# Alimentacion.net
KiCad netlist of a schematic drawn in Altium Designer
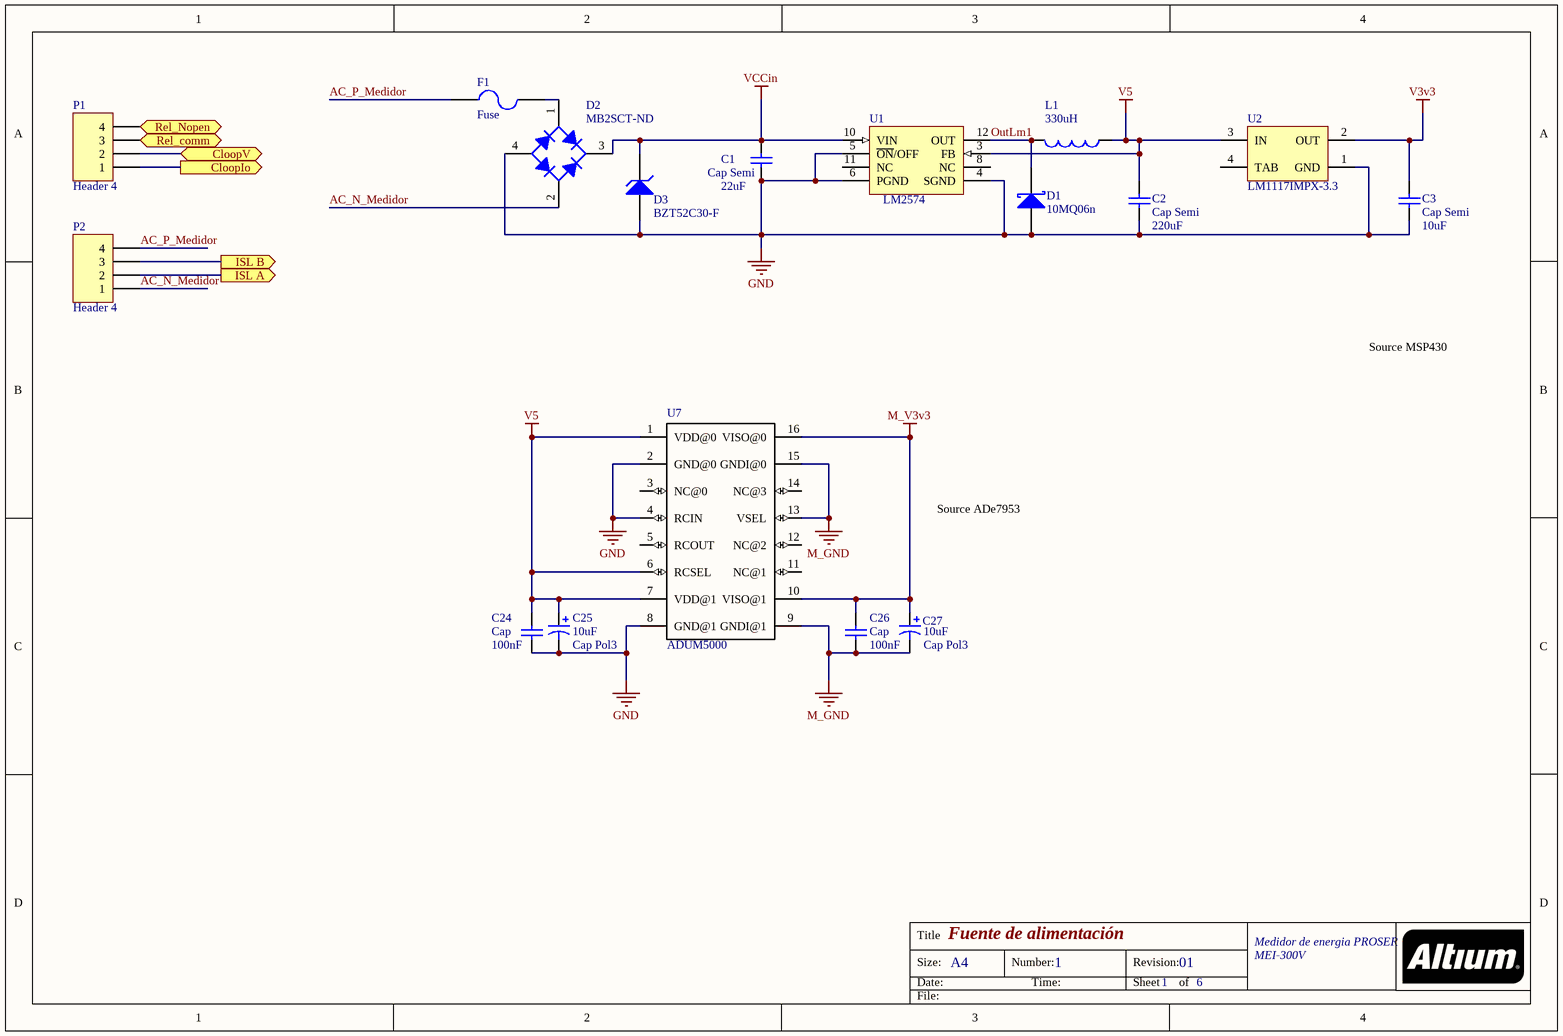
[diagram p0: Alimentacion.SchDoc]

(export (version "E")
  (design (tool "Eeschema 10.0.6"))
  (components
    (comp (ref "C1")
      (value "Cap Semi")
      (footprint "7343")
      (description "Capacitor (Semiconductor SIM Model)")
      (fields (field (name "ALTIUM_VALUE") "22uF") (field (name "PUBLISHER") "Altium Limited"))
      (libsource (lib "Miscellaneous Devices") (part "Cap Semi"))
    )
    (comp (ref "C2")
      (value "Cap Semi")
      (footprint "7343")
      (description "Capacitor (Semiconductor SIM Model)")
      (fields (field (name "ALTIUM_VALUE") "220uF") (field (name "PUBLISHER") "Altium Limited"))
      (libsource (lib "Miscellaneous Devices") (part "Sym"))
    )
    (comp (ref "C3")
      (value "Cap Semi")
      (footprint "3528")
      (description "Capacitor (Semiconductor SIM Model)")
      (fields (field (name "ALTIUM_VALUE") "10uF") (field (name "PUBLISHER") "Altium Limited"))
      (libsource (lib "Miscellaneous Devices") (part "Cap Semi"))
    )
    (comp (ref "C24")
      (value "Cap")
      (footprint "Custom0805")
      (description "Capacitor")
      (fields (field (name "ALTIUM_VALUE") "100nF") (field (name "PUBLISHER") "Altium Limited"))
      (libsource (lib "Miscellaneous Devices") (part "Cap"))
    )
    (comp (ref "C25")
      (value "Cap Pol3")
      (footprint "3528")
      (description "Polarized Capacitor (Surface Mount)")
      (fields (field (name "ALTIUM_VALUE") "10uF") (field (name "PUBLISHER") "Altium Limited"))
      (libsource (lib "Miscellaneous Devices") (part "Cap Pol3"))
    )
    (comp (ref "C26")
      (value "Cap")
      (footprint "Custom0805")
      (description "Capacitor")
      (fields (field (name "ALTIUM_VALUE") "100nF") (field (name "PUBLISHER") "Altium Limited"))
      (libsource (lib "Miscellaneous Devices") (part "Cap"))
    )
    (comp (ref "C27")
      (value "Cap Pol3")
      (footprint "3528")
      (description "Polarized Capacitor (Surface Mount)")
      (fields (field (name "ALTIUM_VALUE") "10uF") (field (name "PUBLISHER") "Altium Limited"))
      (libsource (lib "Miscellaneous Devices") (part "Cap Pol3"))
    )
    (comp (ref "D1")
      (value "10MQ06n")
      (footprint "DO214")
      (description "Schottky Diode")
      (fields (field (name "PUBLISHER") "Altium Limited"))
      (libsource (lib "Miscellaneous Devices") (part "D Schottky"))
    )
    (comp (ref "D2")
      (value "MB2SCT-ND")
      (footprint "SOIC4_M")
      (description "Full Wave Diode Bridge - MB2S")
      (fields (field (name "PUBLISHER") "Altium Limited"))
      (libsource (lib "Miscellaneous Devices") (part "Bridge1"))
    )
    (comp (ref "D3")
      (value "BZT52C30-F")
      (footprint "1N4148W")
      (description "Zener Diode SMD")
      (fields (field (name "PUBLISHER") "Altium Limited"))
      (libsource (lib "Miscellaneous Devices") (part "D Zener"))
    )
    (comp (ref "F1")
      (value "Fuse")
      (footprint "SMD030F")
      (description "SMD030-2CT-ND")
      (fields (field (name "PUBLISHER") "Altium Limited"))
      (libsource (lib "Miscellaneous Devices") (part "Fuse 2"))
    )
    (comp (ref "L1")
      (value "330uH")
      (footprint "PE-526XXNL")
      (description "PE52627NL")
      (fields (field (name "Comment") "Inductor") (field (name "PUBLISHER") "Altium Limited"))
      (libsource (lib "Miscellaneous Devices") (part "Inductor"))
    )
    (comp (ref "P1")
      (value "Header 4")
      (footprint "ConectorPrsr")
      (description "Header, 4-Pin")
      (fields (field (name "PUBLISHER") "Altium Limited"))
      (libsource (lib "Miscellaneous Connectors") (part "Header 4"))
    )
    (comp (ref "P2")
      (value "Header 4")
      (footprint "ConectorPrsr")
      (description "Header, 4-Pin")
      (fields (field (name "PUBLISHER") "Altium Limited"))
      (libsource (lib "Miscellaneous Connectors") (part "Header 4"))
    )
    (comp (ref "U1")
      (value "LM2574")
      (footprint "SOIC127P1033X264-14N")
      (description "Easy Switcher 0.5A Step-Down Voltage Regulator")
      (fields (field (name "PUBLISHER") "Altium Limited"))
      (libsource (lib "ON Semi Power Mgt Voltage Regulator") (part "LM2574N-5"))
    )
    (comp (ref "U2")
      (value "LM1117IMPX-3.3")
      (footprint "MP04A_N")
      (description "800mA Low-Dropout Linear Regulator, 4-pin SOT-223")
      (fields
        (field (name "MANUFACTURER") "National Semiconductor")
        (field (name "PUBLISHER") "Altium Limited")
      )
      (libsource (lib "NSC LDO") (part "LM1117IMPX-3.3"))
    )
    (comp (ref "U7")
      (value "ADUM5000")
      (footprint "*SO16W")
      (description "ADI Isolated DC/DC Converter")
      (fields (field (name "MF") "Analog Devices"))
      (libsource (lib "ADUM5000") (part "ADUM5000"))
    )
  )
  (nets
    (net (code "1") (name "/AC_N_Medidor") (class "Default")
      (node (ref "D2") (pin "2") (pinfunction "C_2") (pintype "passive"))
      (node (ref "P2") (pin "1") (pinfunction "1_1") (pintype "passive"))
    )
    (net (code "2") (name "/AC_P_Medidor") (class "Default")
      (node (ref "F1") (pin "1") (pinfunction "1_1") (pintype "passive"))
      (node (ref "P2") (pin "4") (pinfunction "4_4") (pintype "passive"))
    )
    (net (code "3") (name "/CloopIo") (class "Default")
      (node (ref "P1") (pin "1") (pinfunction "1_1") (pintype "passive"))
    )
    (net (code "4") (name "/CloopV") (class "Default")
      (node (ref "P1") (pin "2") (pinfunction "2_2") (pintype "passive"))
    )
    (net (code "5") (name "/ISL A") (class "Default")
      (node (ref "P2") (pin "2") (pinfunction "2_2") (pintype "passive"))
    )
    (net (code "6") (name "/ISL B") (class "Default")
      (node (ref "P2") (pin "3") (pinfunction "3_3") (pintype "passive"))
    )
    (net (code "7") (name "/OutLm1") (class "Default")
      (node (ref "D1") (pin "2") (pinfunction "K_2") (pintype "passive"))
      (node (ref "L1") (pin "2") (pinfunction "2_2") (pintype "passive"))
      (node (ref "U1") (pin "12") (pinfunction "OUT_12") (pintype "open_emitter"))
    )
    (net (code "8") (name "/Rel_Nopen") (class "Default")
      (node (ref "P1") (pin "4") (pinfunction "4_4") (pintype "passive"))
    )
    (net (code "9") (name "/Rel_comm") (class "Default")
      (node (ref "P1") (pin "3") (pinfunction "3_3") (pintype "passive"))
    )
    (net (code "10") (name "GND") (class "Default")
      (node (ref "C1") (pin "1") (pinfunction "1_1") (pintype "passive"))
      (node (ref "C2") (pin "1") (pinfunction "1_1") (pintype "passive"))
      (node (ref "C24") (pin "1") (pinfunction "1_1") (pintype "passive"))
      (node (ref "C25") (pin "2") (pinfunction "2_2") (pintype "passive"))
      (node (ref "C3") (pin "1") (pinfunction "1_1") (pintype "passive"))
      (node (ref "D1") (pin "1") (pinfunction "A_1") (pintype "passive"))
      (node (ref "D2") (pin "4") (pinfunction "A_4") (pintype "passive"))
      (node (ref "D3") (pin "1") (pinfunction "A_1") (pintype "passive"))
      (node (ref "U1") (pin "4") (pinfunction "SGND_4") (pintype "power_in"))
      (node (ref "U1") (pin "5") (pinfunction "~{ON}/OFF_5") (pintype "passive"))
      (node (ref "U1") (pin "6") (pinfunction "PGND_6") (pintype "power_in"))
      (node (ref "U2") (pin "1") (pinfunction "GND_1") (pintype "power_in"))
      (node (ref "U7") (pin "2") (pinfunction "GND@0_2") (pintype "power_in"))
      (node (ref "U7") (pin "4") (pinfunction "RCIN_4") (pintype "bidirectional"))
      (node (ref "U7") (pin "8") (pinfunction "GND@1_8") (pintype "power_in"))
    )
    (net (code "11") (name "M_GND") (class "Default")
      (node (ref "C26") (pin "1") (pinfunction "1_1") (pintype "passive"))
      (node (ref "C27") (pin "2") (pinfunction "2_2") (pintype "passive"))
      (node (ref "U7") (pin "13") (pinfunction "VSEL_13") (pintype "bidirectional"))
      (node (ref "U7") (pin "15") (pinfunction "GNDI@0_15") (pintype "power_in"))
      (node (ref "U7") (pin "9") (pinfunction "GNDI@1_9") (pintype "power_in"))
    )
    (net (code "12") (name "M_V3v3") (class "Default")
      (node (ref "C26") (pin "2") (pinfunction "2_2") (pintype "passive"))
      (node (ref "C27") (pin "1") (pinfunction "1_1") (pintype "passive"))
      (node (ref "U7") (pin "10") (pinfunction "VISO@1_10") (pintype "passive"))
      (node (ref "U7") (pin "16") (pinfunction "VISO@0_16") (pintype "power_in"))
    )
    (net (code "13") (name "Net-(D2-C-Pad1)") (class "Default")
      (node (ref "D2") (pin "1") (pinfunction "C_1") (pintype "passive"))
      (node (ref "F1") (pin "2") (pinfunction "2_2") (pintype "passive"))
    )
    (net (code "14") (name "V3v3") (class "Default")
      (node (ref "C3") (pin "2") (pinfunction "2_2") (pintype "passive"))
      (node (ref "U2") (pin "2") (pinfunction "OUT_2") (pintype "power_in"))
    )
    (net (code "15") (name "V5") (class "Default")
      (node (ref "C2") (pin "2") (pinfunction "2_2") (pintype "passive"))
      (node (ref "C24") (pin "2") (pinfunction "2_2") (pintype "passive"))
      (node (ref "C25") (pin "1") (pinfunction "1_1") (pintype "passive"))
      (node (ref "L1") (pin "1") (pinfunction "1_1") (pintype "passive"))
      (node (ref "U1") (pin "3") (pinfunction "FB_3") (pintype "input"))
      (node (ref "U2") (pin "3") (pinfunction "IN_3") (pintype "power_in"))
      (node (ref "U7") (pin "1") (pinfunction "VDD@0_1") (pintype "power_in"))
      (node (ref "U7") (pin "6") (pinfunction "RCSEL_6") (pintype "bidirectional"))
      (node (ref "U7") (pin "7") (pinfunction "VDD@1_7") (pintype "passive"))
    )
    (net (code "16") (name "VCCin") (class "Default")
      (node (ref "C1") (pin "2") (pinfunction "2_2") (pintype "passive"))
      (node (ref "D2") (pin "3") (pinfunction "K_3") (pintype "passive"))
      (node (ref "D3") (pin "2") (pinfunction "K_2") (pintype "passive"))
      (node (ref "U1") (pin "10") (pinfunction "VIN_10") (pintype "input"))
    )
    (net (code "17") (name "unconnected-(U1-NC-Pad8)") (class "Default")
      (node (ref "U1") (pin "8") (pinfunction "NC_8") (pintype "passive"))
    )
    (net (code "18") (name "unconnected-(U1-NC-Pad11)") (class "Default")
      (node (ref "U1") (pin "11") (pinfunction "NC_11") (pintype "passive"))
    )
    (net (code "19") (name "unconnected-(U2-TAB-Pad4)") (class "Default")
      (node (ref "U2") (pin "4") (pinfunction "TAB_4") (pintype "power_in"))
    )
    (net (code "20") (name "unconnected-(U7-NC@0-Pad3)") (class "Default")
      (node (ref "U7") (pin "3") (pinfunction "NC@0_3") (pintype "bidirectional"))
    )
    (net (code "21") (name "unconnected-(U7-NC@1-Pad11)") (class "Default")
      (node (ref "U7") (pin "11") (pinfunction "NC@1_11") (pintype "bidirectional"))
    )
    (net (code "22") (name "unconnected-(U7-NC@2-Pad12)") (class "Default")
      (node (ref "U7") (pin "12") (pinfunction "NC@2_12") (pintype "bidirectional"))
    )
    (net (code "23") (name "unconnected-(U7-NC@3-Pad14)") (class "Default")
      (node (ref "U7") (pin "14") (pinfunction "NC@3_14") (pintype "bidirectional"))
    )
    (net (code "24") (name "unconnected-(U7-RCOUT-Pad5)") (class "Default")
      (node (ref "U7") (pin "5") (pinfunction "RCOUT_5") (pintype "bidirectional"))
    )
  )
)
